# openmv-cc.net
KiCad netlist of a schematic drawn in EAGLE
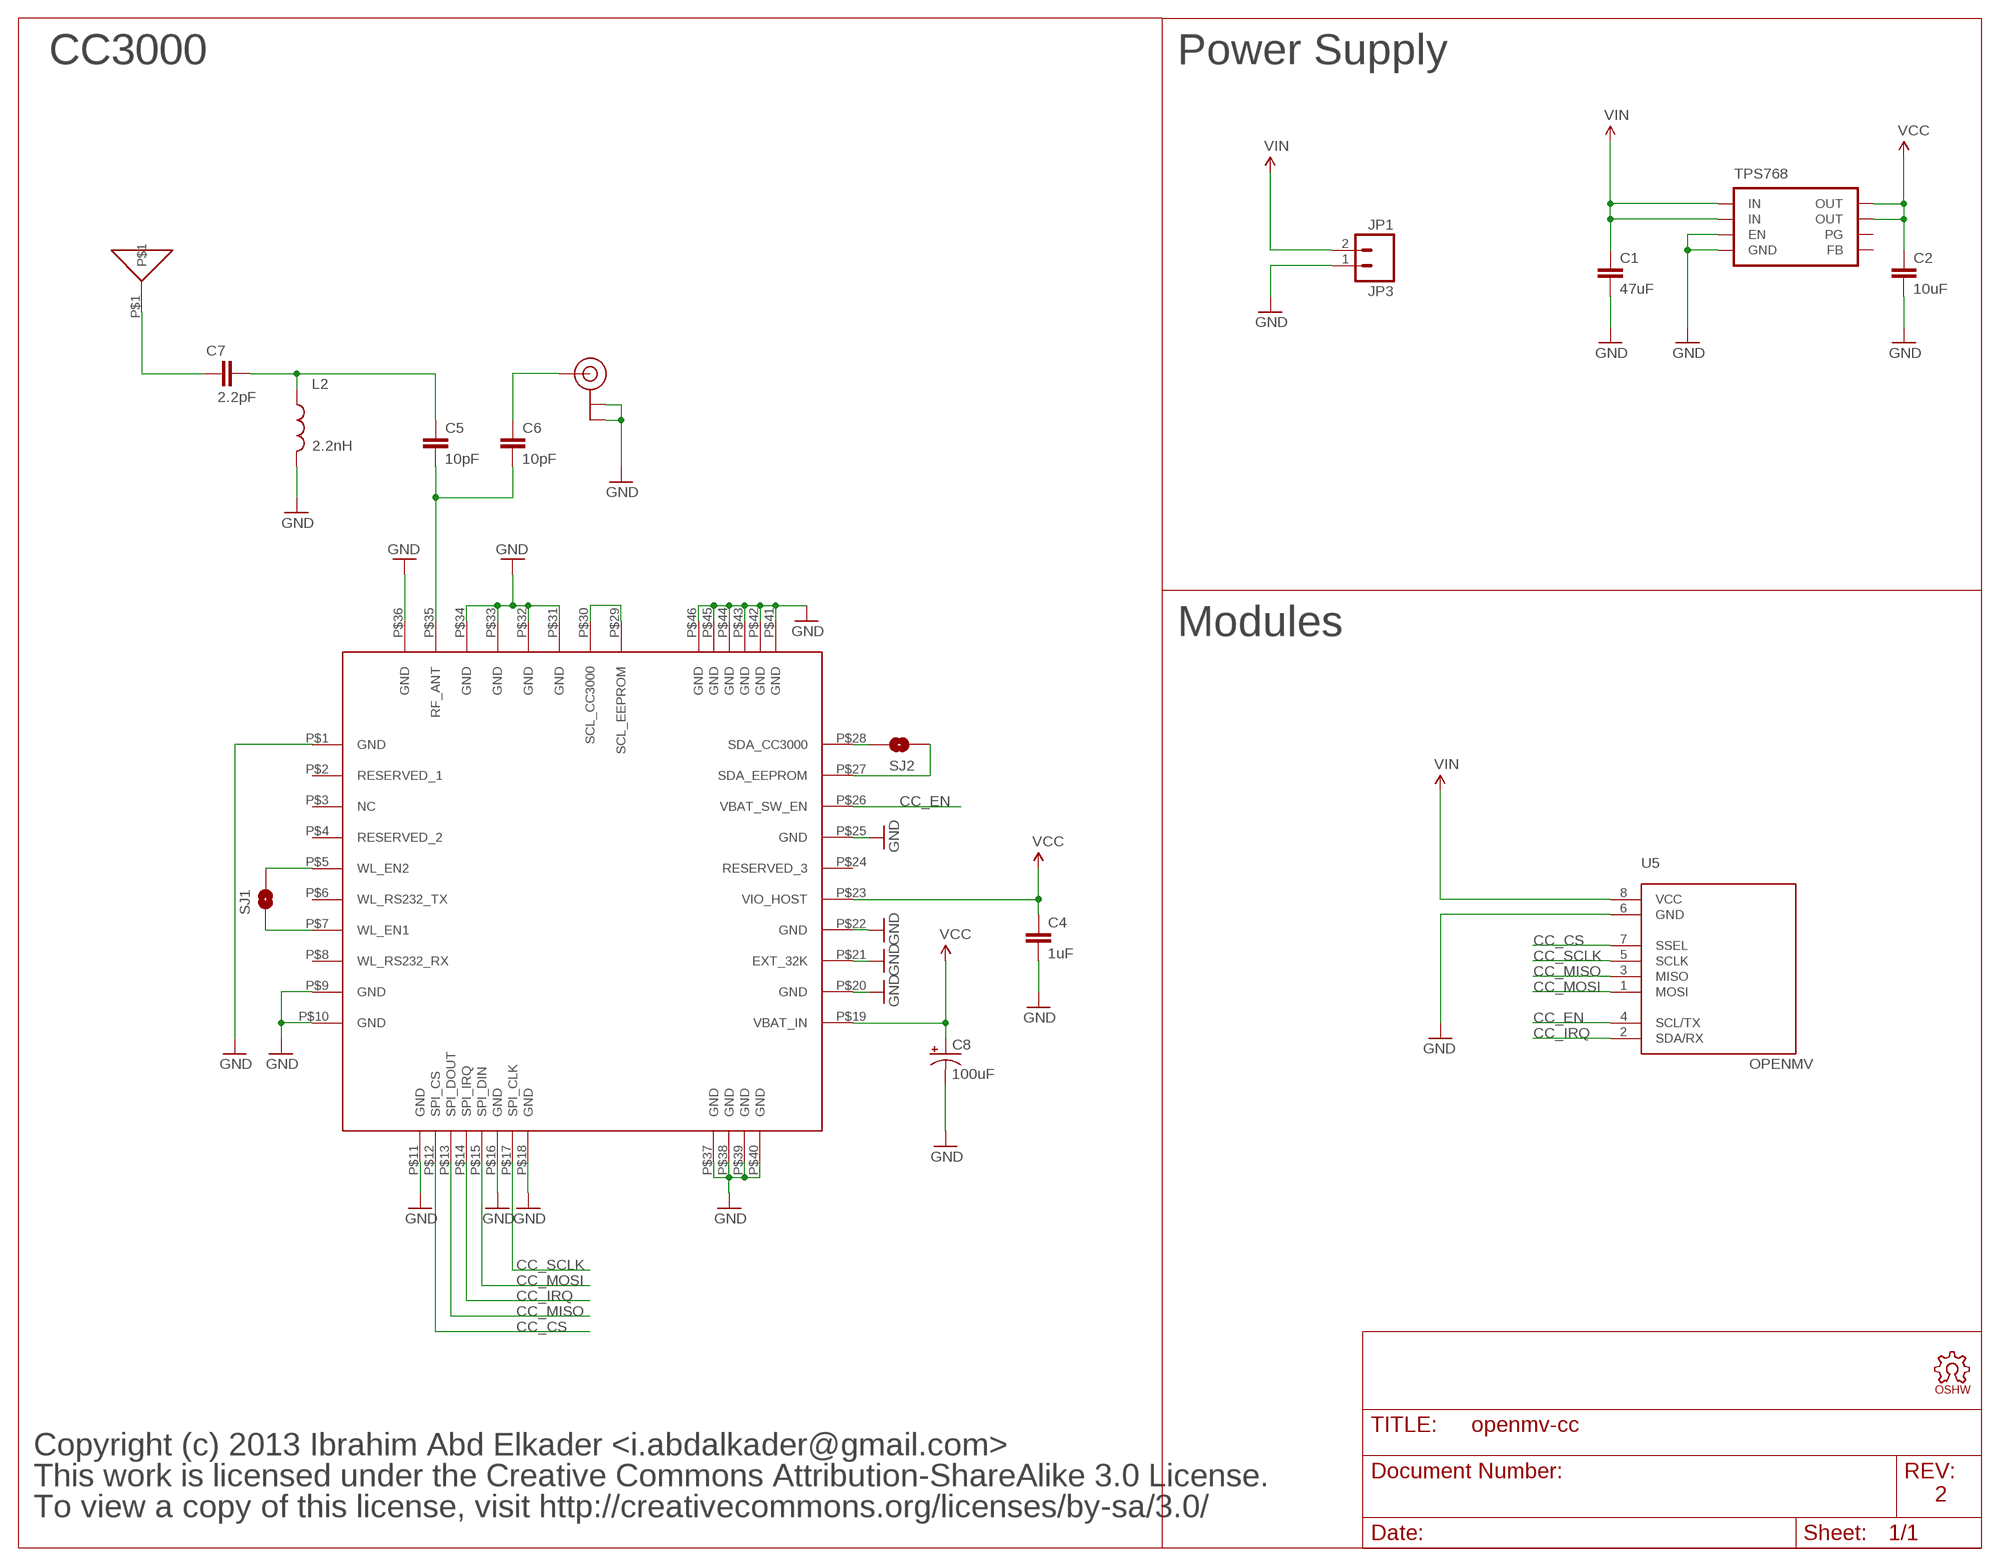
[diagram p0: schematic, sheet 1]

(export (version "E")
  (design (tool "Eeschema 10.0.6"))
  (components
    (comp (ref "C1")
      (value "47uF")
      (footprint "eagle-import:1210")
      (libsource (lib "eagle-import") (part "CAP1210"))
    )
    (comp (ref "C2")
      (value "10uF")
      (footprint "eagle-import:0805")
      (libsource (lib "eagle-import") (part "CAP0805"))
    )
    (comp (ref "C4")
      (value "1uF")
      (footprint "eagle-import:0402-CAP")
      (libsource (lib "eagle-import") (part "CAP0402-CAP"))
    )
    (comp (ref "C5")
      (value "10pF")
      (footprint "eagle-import:0402-CAP")
      (libsource (lib "eagle-import") (part "CAP0402-CAP"))
    )
    (comp (ref "C6")
      (value "10pF")
      (footprint "eagle-import:0402-CAP")
      (libsource (lib "eagle-import") (part "CAP0402-CAP"))
    )
    (comp (ref "C7")
      (value "2.2pF")
      (footprint "eagle-import:0402-CAP")
      (libsource (lib "eagle-import") (part "CAP0402-CAP"))
    )
    (comp (ref "C8")
      (value "100uF")
      (footprint "eagle-import:EIA3528")
      (libsource (lib "eagle-import") (part "CAP_POL3528"))
    )
    (comp (ref "JP1")
      (value "JP3")
      (footprint "eagle-import:JST-2-PTH")
      (libsource (lib "eagle-import") (part "M02JST-PTH-2"))
    )
    (comp (ref "L2")
      (value "2.2nH")
      (footprint "eagle-import:C0402")
      (libsource (lib "eagle-import") (part "INDUCTOR0402"))
    )
    (comp (ref "LOGO1")
      (value "OSHW_LOGO_FILLX0100-NT")
      (footprint "eagle-import:OSHW_FILLX100_NOTEXT")
      (libsource (lib "eagle-import") (part "OSHW_LOGO_FILLX0100-NT"))
    )
    (comp (ref "SJ1")
      (value "SOLDERJUMPERTRACE")
      (footprint "eagle-import:SJ_2S-TRACE")
      (libsource (lib "eagle-import") (part "SOLDERJUMPERTRACE"))
    )
    (comp (ref "SJ2")
      (value "SOLDERJUMPERTRACE")
      (footprint "eagle-import:SJ_2S-TRACE")
      (libsource (lib "eagle-import") (part "SOLDERJUMPERTRACE"))
    )
    (comp (ref "U1")
      (value "CC3000")
      (footprint "eagle-import:CC3000")
      (fields (field (name "AUTHOR") "Matt Bigarani"))
      (libsource (lib "eagle-import") (part "CC3000"))
    )
    (comp (ref "U2")
      (value "ANT-YAGEO")
      (footprint "eagle-import:ANTENNA")
      (libsource (lib "eagle-import") (part "ANT-YAGEO"))
    )
    (comp (ref "U3")
      (value "U.FL")
      (footprint "eagle-import:U.FL")
      (libsource (lib "eagle-import") (part "U.FL"))
    )
    (comp (ref "U4")
      (value "TPS768")
      (footprint "eagle-import:SOIC8")
      (libsource (lib "eagle-import") (part "TPS768"))
    )
    (comp (ref "U5")
      (value "OPENMV")
      (footprint "eagle-import:OPENMV")
      (libsource (lib "eagle-import") (part "OPENMV"))
    )
  )
  (nets
    (net (code "1") (name "/CC_CS") (class "Default")
      (node (ref "U1") (pin "P$12") (pinfunction "SPI_CS_P$12") (pintype "bidirectional"))
      (node (ref "U5") (pin "7") (pinfunction "SSEL_7") (pintype "bidirectional"))
    )
    (net (code "2") (name "/CC_EN") (class "Default")
      (node (ref "U1") (pin "P$26") (pinfunction "VBAT_SW_EN_P$26") (pintype "bidirectional"))
      (node (ref "U5") (pin "4") (pinfunction "SCL/TX_4") (pintype "bidirectional"))
    )
    (net (code "3") (name "/CC_IRQ") (class "Default")
      (node (ref "U1") (pin "P$14") (pinfunction "SPI_IRQ_P$14") (pintype "bidirectional"))
      (node (ref "U5") (pin "2") (pinfunction "SDA/RX_2") (pintype "bidirectional"))
    )
    (net (code "4") (name "/CC_MISO") (class "Default")
      (node (ref "U1") (pin "P$13") (pinfunction "SPI_DOUT_P$13") (pintype "bidirectional"))
      (node (ref "U5") (pin "3") (pinfunction "MISO_3") (pintype "bidirectional"))
    )
    (net (code "5") (name "/CC_MOSI") (class "Default")
      (node (ref "U1") (pin "P$15") (pinfunction "SPI_DIN_P$15") (pintype "bidirectional"))
      (node (ref "U5") (pin "1") (pinfunction "MOSI_1") (pintype "bidirectional"))
    )
    (net (code "6") (name "/CC_SCLK") (class "Default")
      (node (ref "U1") (pin "P$17") (pinfunction "SPI_CLK_P$17") (pintype "bidirectional"))
      (node (ref "U5") (pin "5") (pinfunction "SCLK_5") (pintype "bidirectional"))
    )
    (net (code "7") (name "GND") (class "Default")
      (node (ref "C1") (pin "2") (pinfunction "2_2") (pintype "passive"))
      (node (ref "C2") (pin "2") (pinfunction "2_2") (pintype "passive"))
      (node (ref "C4") (pin "2") (pinfunction "2_2") (pintype "passive"))
      (node (ref "C8") (pin "C") (pinfunction "-_C") (pintype "passive"))
      (node (ref "JP1") (pin "1") (pinfunction "2_1") (pintype "passive"))
      (node (ref "L2") (pin "2") (pinfunction "2_2") (pintype "passive"))
      (node (ref "U1") (pin "P$1") (pinfunction "GND_P$1") (pintype "power_in"))
      (node (ref "U1") (pin "P$10") (pinfunction "GND_P$10") (pintype "power_in"))
      (node (ref "U1") (pin "P$11") (pinfunction "GND_P$11") (pintype "power_in"))
      (node (ref "U1") (pin "P$16") (pinfunction "GND_P$16") (pintype "power_in"))
      (node (ref "U1") (pin "P$18") (pinfunction "GND_P$18") (pintype "power_in"))
      (node (ref "U1") (pin "P$20") (pinfunction "GND_P$20") (pintype "bidirectional"))
      (node (ref "U1") (pin "P$21") (pinfunction "EXT_32K_P$21") (pintype "bidirectional"))
      (node (ref "U1") (pin "P$22") (pinfunction "GND_P$22") (pintype "bidirectional"))
      (node (ref "U1") (pin "P$25") (pinfunction "GND_P$25") (pintype "bidirectional"))
      (node (ref "U1") (pin "P$31") (pinfunction "GND_P$31") (pintype "power_in"))
      (node (ref "U1") (pin "P$32") (pinfunction "GND_P$32") (pintype "power_in"))
      (node (ref "U1") (pin "P$33") (pinfunction "GND_P$33") (pintype "power_in"))
      (node (ref "U1") (pin "P$34") (pinfunction "GND_P$34") (pintype "power_in"))
      (node (ref "U1") (pin "P$36") (pinfunction "GND_P$36") (pintype "passive"))
      (node (ref "U1") (pin "P$37") (pinfunction "GND_P$37") (pintype "power_in"))
      (node (ref "U1") (pin "P$38") (pinfunction "GND_P$38") (pintype "passive"))
      (node (ref "U1") (pin "P$39") (pinfunction "GND_P$39") (pintype "power_in"))
      (node (ref "U1") (pin "P$40") (pinfunction "GND_P$40") (pintype "power_in"))
      (node (ref "U1") (pin "P$41") (pinfunction "GND_P$41") (pintype "power_in"))
      (node (ref "U1") (pin "P$42") (pinfunction "GND_P$42") (pintype "power_in"))
      (node (ref "U1") (pin "P$43") (pinfunction "GND_P$43") (pintype "power_in"))
      (node (ref "U1") (pin "P$44") (pinfunction "GND_P$44") (pintype "power_in"))
      (node (ref "U1") (pin "P$45") (pinfunction "GND_P$45") (pintype "power_in"))
      (node (ref "U1") (pin "P$46") (pinfunction "GND_P$46") (pintype "power_in"))
      (node (ref "U1") (pin "P$9") (pinfunction "GND_P$9") (pintype "bidirectional"))
      (node (ref "U3") (pin "P$1") (pinfunction "GND_P$1") (pintype "bidirectional"))
      (node (ref "U3") (pin "P$2") (pinfunction "GND_P$2") (pintype "bidirectional"))
      (node (ref "U4") (pin "1") (pinfunction "GND_1") (pintype "input"))
      (node (ref "U4") (pin "2") (pinfunction "EN_2") (pintype "input"))
      (node (ref "U5") (pin "6") (pinfunction "GND_6") (pintype "power_in"))
    )
    (net (code "8") (name "Net-(C5-Pad1)") (class "Default")
      (node (ref "C5") (pin "1") (pinfunction "1_1") (pintype "passive"))
      (node (ref "C7") (pin "2") (pinfunction "2_2") (pintype "passive"))
      (node (ref "L2") (pin "1") (pinfunction "1_1") (pintype "passive"))
    )
    (net (code "9") (name "Net-(C7-Pad1)") (class "Default")
      (node (ref "C7") (pin "1") (pinfunction "1_1") (pintype "passive"))
      (node (ref "U2") (pin "P$1") (pinfunction "P$1_P$1") (pintype "bidirectional"))
    )
    (net (code "10") (name "Net-(U1-RF_ANT)") (class "Default")
      (node (ref "C5") (pin "2") (pinfunction "2_2") (pintype "passive"))
      (node (ref "C6") (pin "2") (pinfunction "2_2") (pintype "passive"))
      (node (ref "U1") (pin "P$35") (pinfunction "RF_ANT_P$35") (pintype "bidirectional"))
    )
    (net (code "11") (name "Net-(U1-SCL_CC3000)") (class "Default")
      (node (ref "U1") (pin "P$29") (pinfunction "SCL_EEPROM_P$29") (pintype "power_in"))
      (node (ref "U1") (pin "P$30") (pinfunction "SCL_CC3000_P$30") (pintype "power_in"))
    )
    (net (code "12") (name "Net-(U1-SDA_CC3000)") (class "Default")
      (node (ref "SJ2") (pin "2") (pinfunction "2_2") (pintype "passive"))
      (node (ref "U1") (pin "P$28") (pinfunction "SDA_CC3000_P$28") (pintype "bidirectional"))
    )
    (net (code "13") (name "Net-(U1-SDA_EEPROM)") (class "Default")
      (node (ref "SJ2") (pin "1") (pinfunction "1_1") (pintype "passive"))
      (node (ref "U1") (pin "P$27") (pinfunction "SDA_EEPROM_P$27") (pintype "bidirectional"))
    )
    (net (code "14") (name "Net-(U1-WL_EN1)") (class "Default")
      (node (ref "SJ1") (pin "1") (pinfunction "1_1") (pintype "passive"))
      (node (ref "U1") (pin "P$7") (pinfunction "WL_EN1_P$7") (pintype "bidirectional"))
    )
    (net (code "15") (name "Net-(U1-WL_EN2)") (class "Default")
      (node (ref "SJ1") (pin "2") (pinfunction "2_2") (pintype "passive"))
      (node (ref "U1") (pin "P$5") (pinfunction "WL_EN2_P$5") (pintype "bidirectional"))
    )
    (net (code "16") (name "Net-(U3-SIGNAL)") (class "Default")
      (node (ref "C6") (pin "1") (pinfunction "1_1") (pintype "passive"))
      (node (ref "U3") (pin "P$3") (pinfunction "SIGNAL_P$3") (pintype "bidirectional"))
    )
    (net (code "17") (name "VCC") (class "Default")
      (node (ref "C2") (pin "1") (pinfunction "1_1") (pintype "passive"))
      (node (ref "C4") (pin "1") (pinfunction "1_1") (pintype "passive"))
      (node (ref "C8") (pin "A") (pinfunction "+_A") (pintype "passive"))
      (node (ref "U1") (pin "P$19") (pinfunction "VBAT_IN_P$19") (pintype "bidirectional"))
      (node (ref "U1") (pin "P$23") (pinfunction "VIO_HOST_P$23") (pintype "bidirectional"))
      (node (ref "U4") (pin "5") (pinfunction "OUT_5") (pintype "output"))
      (node (ref "U4") (pin "6") (pinfunction "OUT_6") (pintype "output"))
    )
    (net (code "18") (name "VIN") (class "Default")
      (node (ref "C1") (pin "1") (pinfunction "1_1") (pintype "passive"))
      (node (ref "JP1") (pin "2") (pinfunction "1_2") (pintype "passive"))
      (node (ref "U4") (pin "3") (pinfunction "IN_3") (pintype "input"))
      (node (ref "U4") (pin "4") (pinfunction "IN_4") (pintype "input"))
      (node (ref "U5") (pin "8") (pinfunction "VCC_8") (pintype "power_in"))
    )
    (net (code "19") (name "unconnected-(U1-NC-PadP$3)") (class "Default")
      (node (ref "U1") (pin "P$3") (pinfunction "NC_P$3") (pintype "no_connect"))
    )
    (net (code "20") (name "unconnected-(U1-RESERVED_1-PadP$2)") (class "Default")
      (node (ref "U1") (pin "P$2") (pinfunction "RESERVED_1_P$2") (pintype "bidirectional"))
    )
    (net (code "21") (name "unconnected-(U1-RESERVED_2-PadP$4)") (class "Default")
      (node (ref "U1") (pin "P$4") (pinfunction "RESERVED_2_P$4") (pintype "bidirectional"))
    )
    (net (code "22") (name "unconnected-(U1-RESERVED_3-PadP$24)") (class "Default")
      (node (ref "U1") (pin "P$24") (pinfunction "RESERVED_3_P$24") (pintype "bidirectional"))
    )
    (net (code "23") (name "unconnected-(U1-WL_RS232_RX-PadP$8)") (class "Default")
      (node (ref "U1") (pin "P$8") (pinfunction "WL_RS232_RX_P$8") (pintype "bidirectional"))
    )
    (net (code "24") (name "unconnected-(U1-WL_RS232_TX-PadP$6)") (class "Default")
      (node (ref "U1") (pin "P$6") (pinfunction "WL_RS232_TX_P$6") (pintype "bidirectional"))
    )
    (net (code "25") (name "unconnected-(U4-FB-Pad7)") (class "Default")
      (node (ref "U4") (pin "7") (pinfunction "FB_7") (pintype "bidirectional"))
    )
    (net (code "26") (name "unconnected-(U4-PG-Pad8)") (class "Default")
      (node (ref "U4") (pin "8") (pinfunction "PG_8") (pintype "input"))
    )
  )
)
